# 12_-WIFI_Module_WF60.net
KiCad netlist of a schematic drawn in Altium Designer
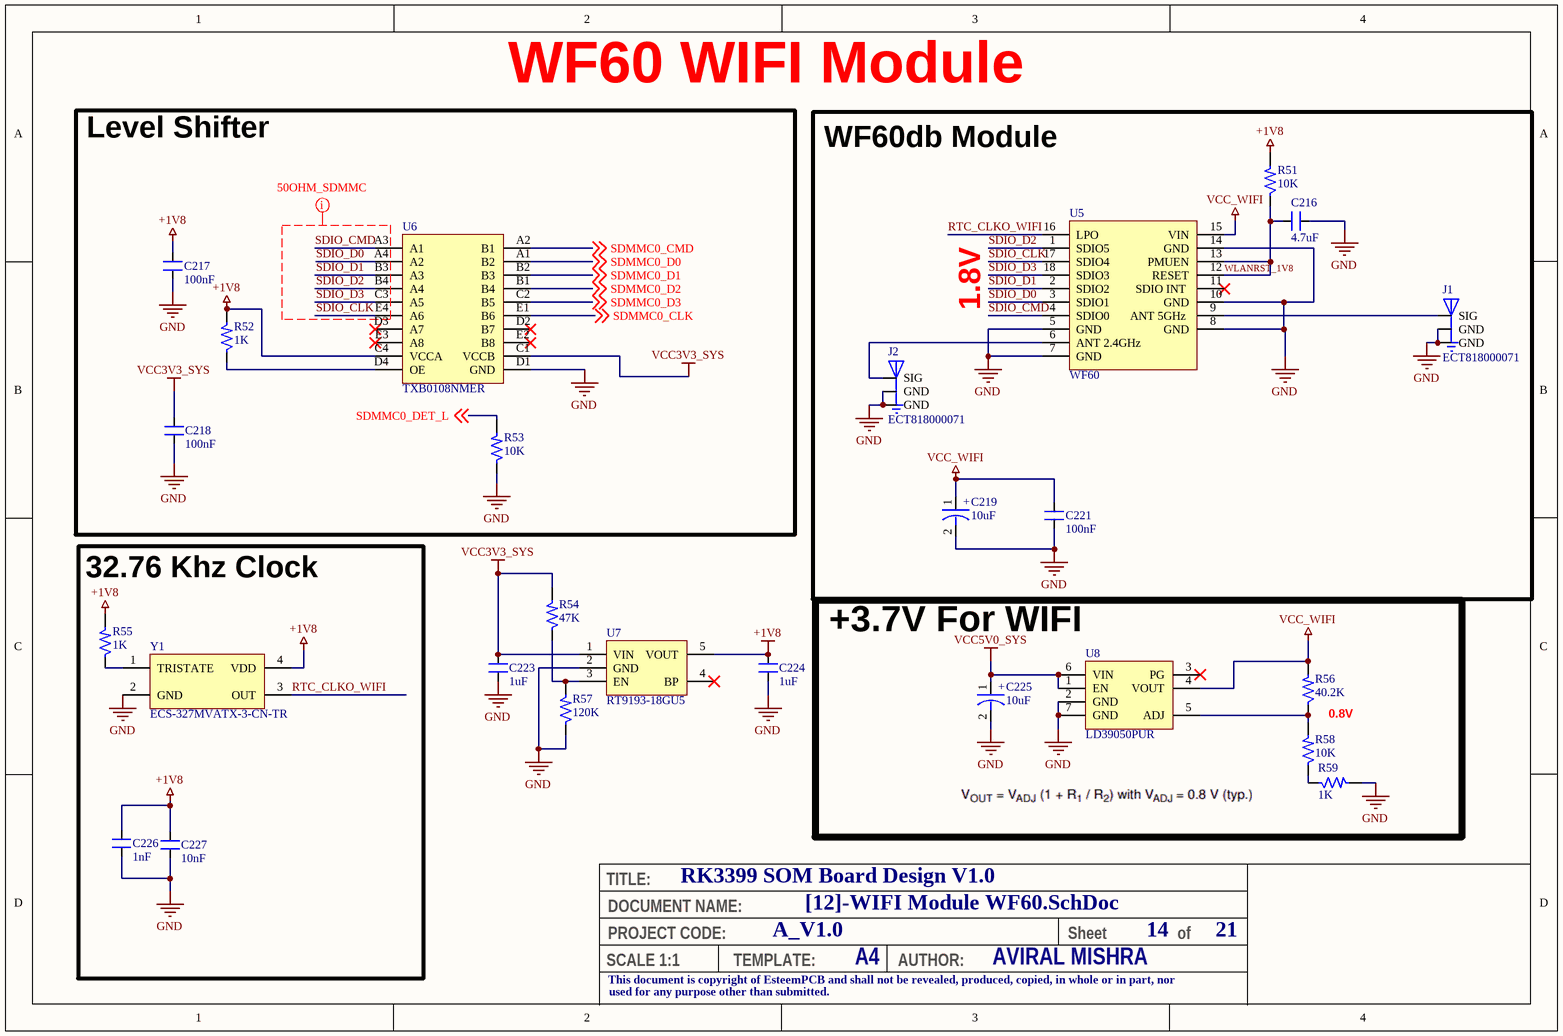
[diagram p0: [12]-WIFI Module WF60.SchDoc]

(export (version "E")
  (design (tool "Eeschema 10.0.6"))
  (components
    (comp (ref "C216")
      (value "4.7uF")
      (footprint "CAP_0402")
      (description "4.7µF ±10% 10V Ceramic Capacitor X5R 0402 (1005 Metric)")
      (fields
        (field (name "MANUFACTURER") "Samsung Electro-Mechanics")
        (field (name "MANUFACTURER PART NUMBER") "CL05A475KP5NRNC")
      )
      (libsource (lib "RK3399 _Module_Intlib") (part "CAP_4.7uF-10V-10%-0402"))
    )
    (comp (ref "C217")
      (value "100nF")
      (footprint "CAP_0402")
      (description "0.1µF ±10% 25V Ceramic Capacitor X7R 0402 (1005 Metric)")
      (fields
        (field (name "MANUFACTURER") "Walsin Technology Corporation")
        (field (name "MANUFACTURER PART NUMBER") "0402B104K250CT")
      )
      (libsource (lib "RK3399 _Module_Intlib") (part "CAP_100nF-25V-10%-0402"))
    )
    (comp (ref "C218")
      (value "100nF")
      (footprint "CAP_0402")
      (description "0.1µF ±10% 25V Ceramic Capacitor X7R 0402 (1005 Metric)")
      (fields
        (field (name "MANUFACTURER") "Walsin Technology Corporation")
        (field (name "MANUFACTURER PART NUMBER") "0402B104K250CT")
      )
      (libsource (lib "RK3399 _Module_Intlib") (part "CAP_100nF-25V-10%-0402"))
    )
    (comp (ref "C219")
      (value "10uF")
      (footprint "CAP-T_1206")
      (description "10µF Molded Tantalum Capacitors 16V 1206 (3216 Metric) 3Ohm")
      (fields
        (field (name "MANUFACTURER") "AVX Corporation")
        (field (name "MANUFACTURER PART NUMBER") "TAJA106K016SNJ")
      )
      (libsource (lib "RK3399 _Module_Intlib") (part "CAP-P_10uF-16V-10%-1206"))
    )
    (comp (ref "C221")
      (value "100nF")
      (footprint "CAP_0402")
      (description "0.1µF ±10% 25V Ceramic Capacitor X7R 0402 (1005 Metric)")
      (fields
        (field (name "MANUFACTURER") "Walsin Technology Corporation")
        (field (name "MANUFACTURER PART NUMBER") "0402B104K250CT")
      )
      (libsource (lib "RK3399 _Module_Intlib") (part "CAP_100nF-25V-10%-0402"))
    )
    (comp (ref "C223")
      (value "1uF")
      (footprint "CAP_0402")
      (description "1µF ±10% 16V Ceramic Capacitor X5R 0402 (1005 Metric)")
      (fields
        (field (name "MANUFACTURER") "Knowles Novacap")
        (field (name "MANUFACTURER PART NUMBER") "0402BW105K160YT")
      )
      (libsource (lib "RK3399 _Module_Schlib") (part "CAP_1uF-16V-10%-0402"))
    )
    (comp (ref "C224")
      (value "1uF")
      (footprint "CAP_0402")
      (description "1µF ±10% 16V Ceramic Capacitor X5R 0402 (1005 Metric)")
      (fields
        (field (name "MANUFACTURER") "Knowles Novacap")
        (field (name "MANUFACTURER PART NUMBER") "0402BW105K160YT")
      )
      (libsource (lib "RK3399 _Module_Schlib") (part "CAP_1uF-16V-10%-0402"))
    )
    (comp (ref "C225")
      (value "10uF")
      (footprint "CAP-T_1206")
      (description "10µF Molded Tantalum Capacitors 16V 1206 (3216 Metric) 3Ohm")
      (fields
        (field (name "MANUFACTURER") "AVX Corporation")
        (field (name "MANUFACTURER PART NUMBER") "TAJA106K016SNJ")
      )
      (libsource (lib "RK3399 _Module_Intlib") (part "CAP-P_10uF-16V-10%-1206"))
    )
    (comp (ref "C226")
      (value "1nF")
      (footprint "CAP_0402")
      (description "1000pF ±10% 16V Ceramic Capacitor X7R 0402 (1005 Metric)")
      (fields
        (field (name "MANUFACTURER") "Yageo")
        (field (name "MANUFACTURER PART NUMBER") "CC0402KRX7R7BB102")
      )
      (libsource (lib "RK3399 _Module_Intlib") (part "CAP_1nF-16V-10%-0402"))
    )
    (comp (ref "C227")
      (value "10nF")
      (footprint "CAP_0402")
      (description "10000pF ±10% 10V Ceramic Capacitor X7R 0402 (1005 Metric)")
      (fields
        (field (name "MANUFACTURER") "AVX Corporation")
        (field (name "MANUFACTURER PART NUMBER") "0402ZC103KAT2A")
      )
      (libsource (lib "RK3399 _Module_Intlib") (part "CAP_10nF-10V-10%-0402"))
    )
    (comp (ref "J1")
      (value "ECT818000071")
      (footprint "CON3_UFL_116_SMD_ST")
      (description "SMD RF Connectors/Coaxial Connectors RoHS")
      (fields (field (name "MANUFACTURER") "ECT"))
      (libsource (lib "RK3399 _Module_Intlib") (part "CON-PLG_3X1-ECT818000071-ST-SMD"))
    )
    (comp (ref "J2")
      (value "ECT818000071")
      (footprint "CON3_UFL_116_SMD_ST")
      (description "SMD RF Connectors/Coaxial Connectors RoHS")
      (fields (field (name "MANUFACTURER") "ECT"))
      (libsource (lib "RK3399 _Module_Intlib") (part "CON-PLG_3X1-ECT818000071-ST-SMD"))
    )
    (comp (ref "R51")
      (value "10K")
      (footprint "RES_0402")
      (description "10 kOhms ±1% 0.1W, 1/10W Chip Resistor 0402 (1005 Metric) Anti-Sulfur Thin Film")
      (fields
        (field (name "MANUFACTURER") "Vishay Beyschlag/Draloric/BC Components")
        (field (name "MANUFACTURER PART NUMBER") "MCS04020C1002FE000")
      )
      (libsource (lib "RK3399 _Module_Intlib") (part "RES_10K-0.1W-1%-0402"))
    )
    (comp (ref "R52")
      (value "1K")
      (footprint "RES_0402")
      (description "1 kOhms ±1% 0.1W, 1/10W Chip Resistor 0402 (1005 Metric) Anti-Sulfur Thin Film")
      (fields
        (field (name "MANUFACTURER") "Vishay Beyschlag/Draloric/BC Components")
        (field (name "MANUFACTURER PART NUMBER") "MCS04020C1001FE000")
      )
      (libsource (lib "RK3399 _Module_Intlib") (part "RES_1K-0.1W-1%-0402"))
    )
    (comp (ref "R53")
      (value "10K")
      (footprint "RES_0201")
      (description "10 kOhms ±1% 0.05W, 1/20W Chip Resistor 0201 (0603 Metric) Thick Film")
      (fields
        (field (name "MANUFACTURER") "Stackpole Electronics Inc")
        (field (name "MANUFACTURER PART NUMBER") "RMCF0201FT10K0")
      )
      (libsource (lib "EsteemPCB_SOM_Course_intlib") (part "RES_10K-0.05W-1%-0201"))
    )
    (comp (ref "R54")
      (value "47K")
      (footprint "RES_0402")
      (description "47 kOhms ±1% 0.1W, 1/10W Chip Resistor 0402 (1005 Metric) Automotive AEC-Q200 Thick Film")
      (fields
        (field (name "MANUFACTURER") "Panasonic Electronic Components")
        (field (name "MANUFACTURER PART NUMBER") "ERJ-2RKF4702X")
      )
      (libsource (lib "RK3399 _Module_Schlib") (part "RES_47K-0.1W-1%-0402"))
    )
    (comp (ref "R55")
      (value "1K")
      (footprint "RES_0402")
      (description "1 kOhms ±1% 0.1W, 1/10W Chip Resistor 0402 (1005 Metric) Anti-Sulfur Thin Film")
      (fields
        (field (name "MANUFACTURER") "Vishay Beyschlag/Draloric/BC Components")
        (field (name "MANUFACTURER PART NUMBER") "MCS04020C1001FE000")
      )
      (libsource (lib "RK3399 _Module_Intlib") (part "RES_1K-0.1W-1%-0402"))
    )
    (comp (ref "R56")
      (value "40.2K")
      (footprint "RES_0805")
      (description "40.2 kOhms ±1% 0.125W, 1/8W Chip Resistor 0805 (2012 Metric) Automotive AEC-Q200 Thick Film")
      (fields
        (field (name "MANUFACTURER") "TE Connectivity")
        (field (name "MANUFACTURER PART NUMBER") "RMCF0805FT40K2")
      )
      (libsource (lib "RK3399 _Module_Intlib") (part "RES_40.2K-0.125W-1%-0805"))
    )
    (comp (ref "R57")
      (value "120K")
      (footprint "RES_0402")
      (description "120 kOhms ±1% 0.1W, 1/10W Chip Resistor 0402 (1005 Metric) Anti-Sulfur Thin Film")
      (fields
        (field (name "MANUFACTURER") "Vishay Beyschlag/Draloric/BC Components")
        (field (name "MANUFACTURER PART NUMBER") "MCS04020C1203FE000")
      )
      (libsource (lib "RK3399 _Module_Schlib") (part "RES_120K-0.1W-1%-0402"))
    )
    (comp (ref "R58")
      (value "10K")
      (footprint "RES_0402")
      (description "10 kOhms ±1% 0.1W, 1/10W Chip Resistor 0402 (1005 Metric) Anti-Sulfur Thin Film")
      (fields
        (field (name "MANUFACTURER") "Vishay Beyschlag/Draloric/BC Components")
        (field (name "MANUFACTURER PART NUMBER") "MCS04020C1002FE000")
      )
      (libsource (lib "RK3399 _Module_Intlib") (part "RES_10K-0.1W-1%-0402"))
    )
    (comp (ref "R59")
      (value "1K")
      (footprint "RES_0402")
      (description "1 kOhms ±1% 0.1W, 1/10W Chip Resistor 0402 (1005 Metric) Anti-Sulfur Thin Film")
      (fields
        (field (name "MANUFACTURER") "Vishay Beyschlag/Draloric/BC Components")
        (field (name "MANUFACTURER PART NUMBER") "MCS04020C1001FE000")
      )
      (libsource (lib "RK3399 _Module_Intlib") (part "RES_1K-0.1W-1%-0402"))
    )
    (comp (ref "U5")
      (value "WF60")
      (footprint "MOD_WF60")
      (description "Amp’ed RF Tech presents the WF60 WiFi dual\r\nband module: 802.11abgn.")
      (fields (field (name "MANUFACTURER") "Amp’ed") (field (name "NYMBLE PART NUMBER") "1EA-AA-0568"))
      (libsource (lib "RK3399 _Module_Intlib") (part "MOD_WF60-SMD"))
    )
    (comp (ref "U6")
      (value "TXB0108NMER")
      (footprint "NFBGA_31.4_125.9X102.36")
      (fields (field (name "MANUFACTURER") "Texas Instruments"))
      (libsource (lib "RK3399 _Module_Intlib") (part "IC_TXB0108NMER"))
    )
    (comp (ref "U7")
      (value "RT9193-18GU5")
      (footprint "SC70-5")
      (description "Linear Voltage Regulator IC 1 Output 300mA SC-70-5")
      (fields (field (name "MANUFACTURER") "Richtek USA Inc."))
      (libsource (lib "RK3399 _Module_Schlib") (part "REG_1.8V-300mA-5.5V-SC70-5"))
    )
    (comp (ref "U8")
      (value "LD39050PUR")
      (footprint "DFN-6_37.4_165_33X15_SMD")
      (description "Adjustable 5.5V 0.8V 500mA DFN-6 Linear Voltage Regulators RoHS")
      (fields
        (field (name "MANUFACTURER") "STMicroelectronics")
        (field (name "NYMBLE PART NUMBER") "1EA-AA-0572")
      )
      (libsource (lib "RK3399 _Module_Intlib") (part "REG_5.5V-0~5.1V-0.5A-2.55W-DFN-6"))
    )
    (comp (ref "Y1")
      (value "ECS-327MVATX-3-CN-TR")
      (footprint "XTAL_57_35X31_SMD")
      (description "32.768kHz XO (Standard) CMOS Oscillator 1.6V ~ 3.6V Enable/Disable 4-SMD, No Lead")
      (fields (field (name "MANUFACTURER") "ECS INC") (field (name "NYMBLE PART NUMBER") "1EA-AA-0561"))
      (libsource (lib "RK3399 _Module_Intlib") (part "XTAL_ECS-327MVATX-2-CN-TR"))
    )
  )
  (nets
    (net (code "1") (name "+1V8") (class "Default")
      (node (ref "C217") (pin "2") (pinfunction "2_2") (pintype "passive"))
      (node (ref "C224") (pin "2") (pinfunction "2_2") (pintype "passive"))
      (node (ref "C226") (pin "2") (pinfunction "2_2") (pintype "passive"))
      (node (ref "C227") (pin "2") (pinfunction "2_2") (pintype "passive"))
      (node (ref "R51") (pin "2") (pinfunction "2_2") (pintype "passive"))
      (node (ref "R52") (pin "2") (pinfunction "2_2") (pintype "passive"))
      (node (ref "R55") (pin "2") (pinfunction "2_2") (pintype "passive"))
      (node (ref "U6") (pin "C4") (pinfunction "VCCA_C4") (pintype "passive"))
      (node (ref "U7") (pin "5") (pinfunction "VOUT_5") (pintype "passive"))
      (node (ref "Y1") (pin "4") (pinfunction "VDD_4") (pintype "passive"))
    )
    (net (code "2") (name "/RTC_CLKO_WIFI") (class "Default")
      (node (ref "U5") (pin "16") (pinfunction "LPO_16") (pintype "passive"))
      (node (ref "Y1") (pin "3") (pinfunction "OUT_3") (pintype "passive"))
    )
    (net (code "3") (name "/SDIO_CLK") (class "Default")
      (node (ref "U5") (pin "17") (pinfunction "SDIO4_17") (pintype "passive"))
      (node (ref "U6") (pin "E4") (pinfunction "A6_E4") (pintype "passive"))
    )
    (net (code "4") (name "/SDIO_CMD") (class "Default")
      (node (ref "U5") (pin "4") (pinfunction "SDIO0_4") (pintype "passive"))
      (node (ref "U6") (pin "A3") (pinfunction "A1_A3") (pintype "passive"))
    )
    (net (code "5") (name "/SDIO_D0") (class "Default")
      (node (ref "U5") (pin "3") (pinfunction "SDIO1_3") (pintype "passive"))
      (node (ref "U6") (pin "A4") (pinfunction "A2_A4") (pintype "passive"))
    )
    (net (code "6") (name "/SDIO_D1") (class "Default")
      (node (ref "U5") (pin "2") (pinfunction "SDIO2_2") (pintype "passive"))
      (node (ref "U6") (pin "B3") (pinfunction "A3_B3") (pintype "passive"))
    )
    (net (code "7") (name "/SDIO_D2") (class "Default")
      (node (ref "U5") (pin "1") (pinfunction "SDIO5_1") (pintype "passive"))
      (node (ref "U6") (pin "B4") (pinfunction "A4_B4") (pintype "passive"))
    )
    (net (code "8") (name "/SDIO_D3") (class "Default")
      (node (ref "U5") (pin "18") (pinfunction "SDIO3_18") (pintype "passive"))
      (node (ref "U6") (pin "C3") (pinfunction "A5_C3") (pintype "passive"))
    )
    (net (code "9") (name "/WLANRST_1V8") (class "Default")
      (node (ref "C216") (pin "2") (pinfunction "2_2") (pintype "passive"))
      (node (ref "R51") (pin "1") (pinfunction "1_1") (pintype "passive"))
      (node (ref "U5") (pin "12") (pinfunction "RESET_12") (pintype "passive"))
      (node (ref "U5") (pin "13") (pinfunction "PMUEN_13") (pintype "passive"))
    )
    (net (code "10") (name "GND") (class "Default")
      (node (ref "C216") (pin "1") (pinfunction "1_1") (pintype "passive"))
      (node (ref "C217") (pin "1") (pinfunction "1_1") (pintype "passive"))
      (node (ref "C218") (pin "1") (pinfunction "1_1") (pintype "passive"))
      (node (ref "C219") (pin "2") (pinfunction "2_2") (pintype "passive"))
      (node (ref "C221") (pin "1") (pinfunction "1_1") (pintype "passive"))
      (node (ref "C223") (pin "1") (pinfunction "1_1") (pintype "passive"))
      (node (ref "C224") (pin "1") (pinfunction "1_1") (pintype "passive"))
      (node (ref "C225") (pin "2") (pinfunction "2_2") (pintype "passive"))
      (node (ref "C226") (pin "1") (pinfunction "1_1") (pintype "passive"))
      (node (ref "C227") (pin "1") (pinfunction "1_1") (pintype "passive"))
      (node (ref "J1") (pin "1") (pinfunction "GND_1") (pintype "passive"))
      (node (ref "J1") (pin "3") (pinfunction "GND_3") (pintype "passive"))
      (node (ref "J2") (pin "1") (pinfunction "GND_1") (pintype "passive"))
      (node (ref "J2") (pin "3") (pinfunction "GND_3") (pintype "passive"))
      (node (ref "R53") (pin "1") (pinfunction "1_1") (pintype "passive"))
      (node (ref "R57") (pin "1") (pinfunction "1_1") (pintype "passive"))
      (node (ref "R59") (pin "2") (pinfunction "2_2") (pintype "passive"))
      (node (ref "U5") (pin "10") (pinfunction "GND_10") (pintype "passive"))
      (node (ref "U5") (pin "14") (pinfunction "GND_14") (pintype "passive"))
      (node (ref "U5") (pin "5") (pinfunction "GND_5") (pintype "passive"))
      (node (ref "U5") (pin "7") (pinfunction "GND_7") (pintype "passive"))
      (node (ref "U5") (pin "8") (pinfunction "GND_8") (pintype "passive"))
      (node (ref "U6") (pin "D1") (pinfunction "GND_D1") (pintype "passive"))
      (node (ref "U7") (pin "2") (pinfunction "GND_2") (pintype "passive"))
      (node (ref "U8") (pin "2") (pinfunction "GND_2") (pintype "passive"))
      (node (ref "U8") (pin "7") (pinfunction "GND_7") (pintype "passive"))
      (node (ref "Y1") (pin "2") (pinfunction "GND_2") (pintype "passive"))
    )
    (net (code "11") (name "Net-(J1-SIG)") (class "Default")
      (node (ref "J1") (pin "2") (pinfunction "SIG_2") (pintype "passive"))
      (node (ref "U5") (pin "9") (pinfunction "ANT_5GHz_9") (pintype "passive"))
    )
    (net (code "12") (name "Net-(J2-SIG)") (class "Default")
      (node (ref "J2") (pin "2") (pinfunction "SIG_2") (pintype "passive"))
      (node (ref "U5") (pin "6") (pinfunction "ANT_2.4GHz_6") (pintype "passive"))
    )
    (net (code "13") (name "Net-(R58-Pad1)") (class "Default")
      (node (ref "R58") (pin "1") (pinfunction "1_1") (pintype "passive"))
      (node (ref "R59") (pin "1") (pinfunction "1_1") (pintype "passive"))
    )
    (net (code "14") (name "Net-(U6-OE)") (class "Default")
      (node (ref "R52") (pin "1") (pinfunction "1_1") (pintype "passive"))
      (node (ref "U6") (pin "D4") (pinfunction "OE_D4") (pintype "passive"))
    )
    (net (code "15") (name "Net-(U7-EN)") (class "Default")
      (node (ref "R54") (pin "1") (pinfunction "1_1") (pintype "passive"))
      (node (ref "R57") (pin "2") (pinfunction "2_2") (pintype "passive"))
      (node (ref "U7") (pin "3") (pinfunction "EN_3") (pintype "passive"))
    )
    (net (code "16") (name "Net-(U8-ADJ)") (class "Default")
      (node (ref "R56") (pin "1") (pinfunction "1_1") (pintype "passive"))
      (node (ref "R58") (pin "2") (pinfunction "2_2") (pintype "passive"))
      (node (ref "U8") (pin "5") (pinfunction "ADJ_5") (pintype "passive"))
    )
    (net (code "17") (name "Net-(Y1-TRISTATE)") (class "Default")
      (node (ref "R55") (pin "1") (pinfunction "1_1") (pintype "passive"))
      (node (ref "Y1") (pin "1") (pinfunction "TRISTATE_1") (pintype "passive"))
    )
    (net (code "18") (name "SDMMC0_CLK") (class "Default")
      (node (ref "U6") (pin "E1") (pinfunction "B6_E1") (pintype "passive"))
    )
    (net (code "19") (name "SDMMC0_CMD") (class "Default")
      (node (ref "U6") (pin "A2") (pinfunction "B1_A2") (pintype "passive"))
    )
    (net (code "20") (name "SDMMC0_D0") (class "Default")
      (node (ref "U6") (pin "A1") (pinfunction "B2_A1") (pintype "passive"))
    )
    (net (code "21") (name "SDMMC0_D1") (class "Default")
      (node (ref "U6") (pin "B2") (pinfunction "B3_B2") (pintype "passive"))
    )
    (net (code "22") (name "SDMMC0_D2") (class "Default")
      (node (ref "U6") (pin "B1") (pinfunction "B4_B1") (pintype "passive"))
    )
    (net (code "23") (name "SDMMC0_D3") (class "Default")
      (node (ref "U6") (pin "C2") (pinfunction "B5_C2") (pintype "passive"))
    )
    (net (code "24") (name "SDMMC0_DET_L") (class "Default")
      (node (ref "R53") (pin "2") (pinfunction "2_2") (pintype "passive"))
    )
    (net (code "25") (name "VCC3V3_SYS") (class "Default")
      (node (ref "C218") (pin "2") (pinfunction "2_2") (pintype "passive"))
      (node (ref "C223") (pin "2") (pinfunction "2_2") (pintype "passive"))
      (node (ref "R54") (pin "2") (pinfunction "2_2") (pintype "passive"))
      (node (ref "U6") (pin "C1") (pinfunction "VCCB_C1") (pintype "passive"))
      (node (ref "U7") (pin "1") (pinfunction "VIN_1") (pintype "passive"))
    )
    (net (code "26") (name "VCC5V0_SYS") (class "Default")
      (node (ref "C225") (pin "1") (pinfunction "1_1") (pintype "passive"))
      (node (ref "U8") (pin "1") (pinfunction "EN_1") (pintype "passive"))
      (node (ref "U8") (pin "6") (pinfunction "VIN_6") (pintype "passive"))
    )
    (net (code "27") (name "VCC_WIFI") (class "Default")
      (node (ref "C219") (pin "1") (pinfunction "1_1") (pintype "passive"))
      (node (ref "C221") (pin "2") (pinfunction "2_2") (pintype "passive"))
      (node (ref "R56") (pin "2") (pinfunction "2_2") (pintype "passive"))
      (node (ref "U5") (pin "15") (pinfunction "VIN_15") (pintype "passive"))
      (node (ref "U8") (pin "4") (pinfunction "VOUT_4") (pintype "passive"))
    )
    (net (code "28") (name "unconnected-(U5-SDIO_INT-Pad11)") (class "Default")
      (node (ref "U5") (pin "11") (pinfunction "SDIO_INT_11") (pintype "passive+no_connect"))
    )
    (net (code "29") (name "unconnected-(U6-A7-PadD3)") (class "Default")
      (node (ref "U6") (pin "D3") (pinfunction "A7_D3") (pintype "passive+no_connect"))
    )
    (net (code "30") (name "unconnected-(U6-A8-PadE3)") (class "Default")
      (node (ref "U6") (pin "E3") (pinfunction "A8_E3") (pintype "passive+no_connect"))
    )
    (net (code "31") (name "unconnected-(U6-B7-PadD2)") (class "Default")
      (node (ref "U6") (pin "D2") (pinfunction "B7_D2") (pintype "passive+no_connect"))
    )
    (net (code "32") (name "unconnected-(U6-B8-PadE2)") (class "Default")
      (node (ref "U6") (pin "E2") (pinfunction "B8_E2") (pintype "passive+no_connect"))
    )
    (net (code "33") (name "unconnected-(U7-BP-Pad4)") (class "Default")
      (node (ref "U7") (pin "4") (pinfunction "BP_4") (pintype "passive+no_connect"))
    )
    (net (code "34") (name "unconnected-(U8-PG-Pad3)") (class "Default")
      (node (ref "U8") (pin "3") (pinfunction "PG_3") (pintype "passive+no_connect"))
    )
  )
)
